# 512kB-v11.net
KiCad netlist of a schematic drawn in EAGLE
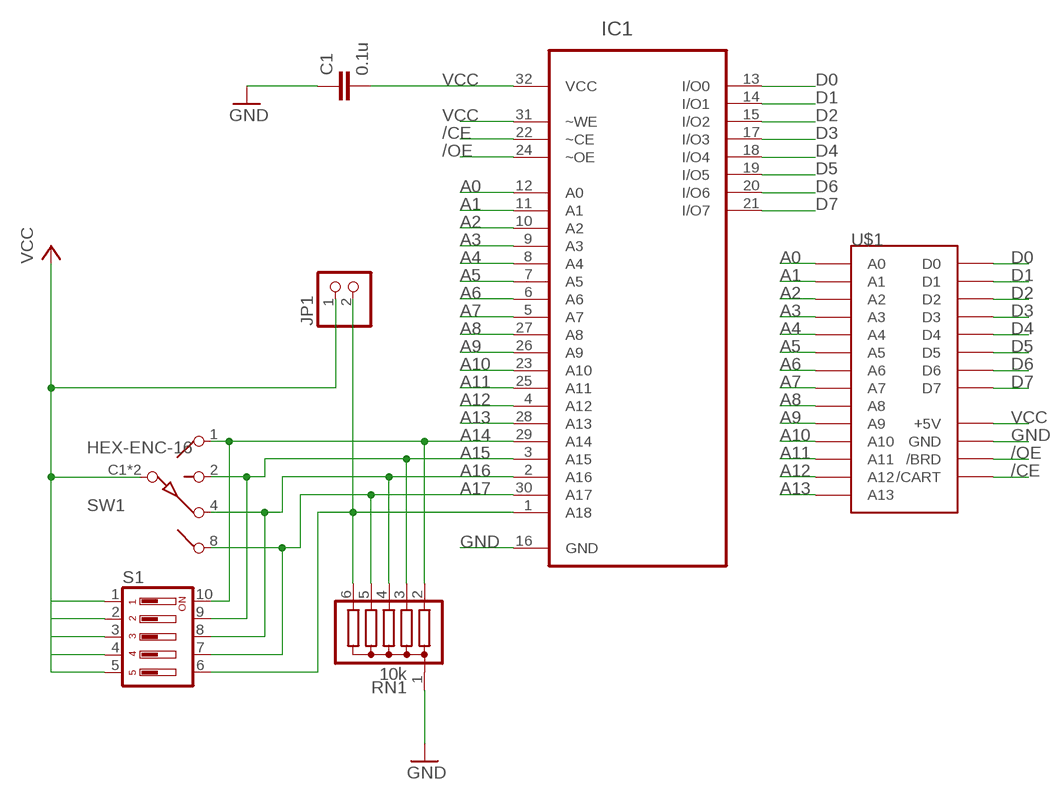
[diagram p0: schematic, sheet 1]

(export (version "E")
  (design (tool "Eeschema 10.0.6"))
  (components
    (comp (ref "C1")
      (value "0.1u")
      (footprint "eagle-import:C050-024X044")
      (libsource (lib "eagle-import") (part "C-EU050-024X044"))
    )
    (comp (ref "IC1")
      (value "AT29C040")
      (footprint "eagle-import:DIP254P1524X482-32")
      (libsource (lib "eagle-import") (part "AT29C040"))
    )
    (comp (ref "JP1")
      (value "PINHD-1X2")
      (footprint "eagle-import:1X02")
      (libsource (lib "eagle-import") (part "PINHD-1X2"))
    )
    (comp (ref "RN1")
      (value "10k")
      (footprint "eagle-import:SIL6")
      (libsource (lib "eagle-import") (part "G05R"))
    )
    (comp (ref "S1")
      (value "DIP05YL")
      (footprint "eagle-import:DIP05YL")
      (libsource (lib "eagle-import") (part "DIP05YL"))
    )
    (comp (ref "SW1")
      (value "HEX-ENC-16")
      (footprint "eagle-import:SW-C16")
      (libsource (lib "eagle-import") (part "SW-C16"))
    )
    (comp (ref "U$1")
      (value "TVC-CARD+")
      (footprint "eagle-import:TVC-CART-CARD")
      (libsource (lib "eagle-import") (part "TVC-CARD+"))
    )
  )
  (nets
    (net (code "1") (name "/A0") (class "Default")
      (node (ref "IC1") (pin "12") (pinfunction "A0_12") (pintype "input"))
      (node (ref "U$1") (pin "TOP25") (pinfunction "A0_TOP25") (pintype "bidirectional"))
    )
    (net (code "2") (name "/A1") (class "Default")
      (node (ref "IC1") (pin "11") (pinfunction "A1_11") (pintype "input"))
      (node (ref "U$1") (pin "TOP2") (pinfunction "A1_TOP2") (pintype "bidirectional"))
    )
    (net (code "3") (name "/A2") (class "Default")
      (node (ref "IC1") (pin "10") (pinfunction "A2_10") (pintype "input"))
      (node (ref "U$1") (pin "TOP24") (pinfunction "A2_TOP24") (pintype "bidirectional"))
    )
    (net (code "4") (name "/A3") (class "Default")
      (node (ref "IC1") (pin "9") (pinfunction "A3_9") (pintype "input"))
      (node (ref "U$1") (pin "TOP1") (pinfunction "A3_TOP1") (pintype "bidirectional"))
    )
    (net (code "5") (name "/A4") (class "Default")
      (node (ref "IC1") (pin "8") (pinfunction "A4_8") (pintype "input"))
      (node (ref "U$1") (pin "TOP21") (pinfunction "A4_TOP21") (pintype "bidirectional"))
    )
    (net (code "6") (name "/A5") (class "Default")
      (node (ref "IC1") (pin "7") (pinfunction "A5_7") (pintype "input"))
      (node (ref "U$1") (pin "TOP14") (pinfunction "A5_TOP14") (pintype "bidirectional"))
    )
    (net (code "7") (name "/A6") (class "Default")
      (node (ref "IC1") (pin "6") (pinfunction "A6_6") (pintype "input"))
      (node (ref "U$1") (pin "TOP18") (pinfunction "A6_TOP18") (pintype "bidirectional"))
    )
    (net (code "8") (name "/A7") (class "Default")
      (node (ref "IC1") (pin "5") (pinfunction "A7_5") (pintype "input"))
      (node (ref "U$1") (pin "TOP17") (pinfunction "A7_TOP17") (pintype "bidirectional"))
    )
    (net (code "9") (name "/A8") (class "Default")
      (node (ref "IC1") (pin "27") (pinfunction "A8_27") (pintype "input"))
      (node (ref "U$1") (pin "TOP15") (pinfunction "A8_TOP15") (pintype "bidirectional"))
    )
    (net (code "10") (name "/A9") (class "Default")
      (node (ref "IC1") (pin "26") (pinfunction "A9_26") (pintype "input"))
      (node (ref "U$1") (pin "TOP19") (pinfunction "A9_TOP19") (pintype "bidirectional"))
    )
    (net (code "11") (name "/A10") (class "Default")
      (node (ref "IC1") (pin "23") (pinfunction "A10_23") (pintype "input"))
      (node (ref "U$1") (pin "TOP22") (pinfunction "A10_TOP22") (pintype "bidirectional"))
    )
    (net (code "12") (name "/A11") (class "Default")
      (node (ref "IC1") (pin "25") (pinfunction "A11_25") (pintype "input"))
      (node (ref "U$1") (pin "TOP20") (pinfunction "A11_TOP20") (pintype "bidirectional"))
    )
    (net (code "13") (name "/A12") (class "Default")
      (node (ref "IC1") (pin "4") (pinfunction "A12_4") (pintype "input"))
      (node (ref "U$1") (pin "TOP16") (pinfunction "A12_TOP16") (pintype "bidirectional"))
    )
    (net (code "14") (name "/A13") (class "Default")
      (node (ref "IC1") (pin "28") (pinfunction "A13_28") (pintype "input"))
      (node (ref "U$1") (pin "TOP23") (pinfunction "A13_TOP23") (pintype "bidirectional"))
    )
    (net (code "15") (name "/A14") (class "Default")
      (node (ref "IC1") (pin "29") (pinfunction "A14_29") (pintype "input"))
      (node (ref "RN1") (pin "2") (pinfunction "2_2") (pintype "passive"))
      (node (ref "S1") (pin "10") (pinfunction "10_10") (pintype "passive"))
      (node (ref "SW1") (pin "1") (pinfunction "1_1") (pintype "passive"))
    )
    (net (code "16") (name "/A15") (class "Default")
      (node (ref "IC1") (pin "3") (pinfunction "A15_3") (pintype "input"))
      (node (ref "RN1") (pin "3") (pinfunction "3_3") (pintype "passive"))
      (node (ref "S1") (pin "9") (pinfunction "9_9") (pintype "passive"))
      (node (ref "SW1") (pin "2") (pinfunction "2_2") (pintype "passive"))
    )
    (net (code "17") (name "/A16") (class "Default")
      (node (ref "IC1") (pin "2") (pinfunction "A16_2") (pintype "input"))
      (node (ref "RN1") (pin "4") (pinfunction "4_4") (pintype "passive"))
      (node (ref "S1") (pin "8") (pinfunction "8_8") (pintype "passive"))
      (node (ref "SW1") (pin "4") (pinfunction "4_4") (pintype "passive"))
    )
    (net (code "18") (name "/A17") (class "Default")
      (node (ref "IC1") (pin "30") (pinfunction "A17_30") (pintype "input"))
      (node (ref "RN1") (pin "5") (pinfunction "5_5") (pintype "passive"))
      (node (ref "S1") (pin "7") (pinfunction "7_7") (pintype "passive"))
      (node (ref "SW1") (pin "8") (pinfunction "8_8") (pintype "passive"))
    )
    (net (code "19") (name "/D0") (class "Default")
      (node (ref "IC1") (pin "13") (pinfunction "I/O0_13") (pintype "bidirectional"))
      (node (ref "U$1") (pin "TOP4") (pinfunction "D0_TOP4") (pintype "bidirectional"))
    )
    (net (code "20") (name "/D1") (class "Default")
      (node (ref "IC1") (pin "14") (pinfunction "I/O1_14") (pintype "bidirectional"))
      (node (ref "U$1") (pin "TOP5") (pinfunction "D1_TOP5") (pintype "bidirectional"))
    )
    (net (code "21") (name "/D2") (class "Default")
      (node (ref "IC1") (pin "15") (pinfunction "I/O2_15") (pintype "bidirectional"))
      (node (ref "U$1") (pin "TOP6") (pinfunction "D2_TOP6") (pintype "bidirectional"))
    )
    (net (code "22") (name "/D3") (class "Default")
      (node (ref "IC1") (pin "17") (pinfunction "I/O3_17") (pintype "bidirectional"))
      (node (ref "U$1") (pin "TOP7") (pinfunction "D3_TOP7") (pintype "bidirectional"))
    )
    (net (code "23") (name "/D4") (class "Default")
      (node (ref "IC1") (pin "18") (pinfunction "I/O4_18") (pintype "bidirectional"))
      (node (ref "U$1") (pin "TOP8") (pinfunction "D4_TOP8") (pintype "bidirectional"))
    )
    (net (code "24") (name "/D5") (class "Default")
      (node (ref "IC1") (pin "19") (pinfunction "I/O5_19") (pintype "bidirectional"))
      (node (ref "U$1") (pin "TOP9") (pinfunction "D5_TOP9") (pintype "bidirectional"))
    )
    (net (code "25") (name "/D6") (class "Default")
      (node (ref "IC1") (pin "20") (pinfunction "I/O6_20") (pintype "bidirectional"))
      (node (ref "U$1") (pin "TOP10") (pinfunction "D6_TOP10") (pintype "bidirectional"))
    )
    (net (code "26") (name "/D7") (class "Default")
      (node (ref "IC1") (pin "21") (pinfunction "I/O7_21") (pintype "bidirectional"))
      (node (ref "U$1") (pin "TOP3") (pinfunction "D7_TOP3") (pintype "bidirectional"))
    )
    (net (code "27") (name "/{slash}CE") (class "Default")
      (node (ref "IC1") (pin "22") (pinfunction "~{CE}_22") (pintype "input"))
      (node (ref "U$1") (pin "BTM23") (pinfunction "/CART_BTM23") (pintype "bidirectional"))
    )
    (net (code "28") (name "/{slash}OE") (class "Default")
      (node (ref "IC1") (pin "24") (pinfunction "~{OE}_24") (pintype "input"))
      (node (ref "U$1") (pin "BTM24") (pinfunction "/BRD_BTM24") (pintype "bidirectional"))
    )
    (net (code "29") (name "GND") (class "Default")
      (node (ref "C1") (pin "1") (pinfunction "1_1") (pintype "passive"))
      (node (ref "IC1") (pin "16") (pinfunction "GND_16") (pintype "passive"))
      (node (ref "RN1") (pin "1") (pinfunction "1_1") (pintype "passive"))
      (node (ref "U$1") (pin "BTM1") (pinfunction "GND_BTM1") (pintype "power_in"))
      (node (ref "U$1") (pin "BTM2") (pinfunction "GND_BTM2") (pintype "power_in"))
      (node (ref "U$1") (pin "BTM3") (pinfunction "GND_BTM3") (pintype "power_in"))
      (node (ref "U$1") (pin "BTM4") (pinfunction "GND_BTM4") (pintype "power_in"))
      (node (ref "U$1") (pin "BTM5") (pinfunction "GND_BTM5") (pintype "power_in"))
      (node (ref "U$1") (pin "BTM6") (pinfunction "GND_BTM6") (pintype "power_in"))
      (node (ref "U$1") (pin "BTM7") (pinfunction "GND_BTM7") (pintype "power_in"))
      (node (ref "U$1") (pin "BTM8") (pinfunction "GND_BTM8") (pintype "power_in"))
    )
    (net (code "30") (name "Net-(IC1-A18)") (class "Default")
      (node (ref "IC1") (pin "1") (pinfunction "A18_1") (pintype "input"))
      (node (ref "JP1") (pin "2") (pinfunction "2_2") (pintype "passive"))
      (node (ref "RN1") (pin "6") (pinfunction "6_6") (pintype "passive"))
      (node (ref "S1") (pin "6") (pinfunction "6_6") (pintype "passive"))
    )
    (net (code "31") (name "VCC") (class "Default")
      (node (ref "C1") (pin "2") (pinfunction "2_2") (pintype "passive"))
      (node (ref "IC1") (pin "31") (pinfunction "~{WE}_31") (pintype "input"))
      (node (ref "IC1") (pin "32") (pinfunction "VCC_32") (pintype "power_in"))
      (node (ref "JP1") (pin "1") (pinfunction "1_1") (pintype "passive"))
      (node (ref "S1") (pin "1") (pinfunction "1_1") (pintype "passive"))
      (node (ref "S1") (pin "2") (pinfunction "2_2") (pintype "passive"))
      (node (ref "S1") (pin "3") (pinfunction "3_3") (pintype "passive"))
      (node (ref "S1") (pin "4") (pinfunction "4_4") (pintype "passive"))
      (node (ref "S1") (pin "5") (pinfunction "5_5") (pintype "passive"))
      (node (ref "SW1") (pin "C1") (pinfunction "C_C1") (pintype "passive"))
      (node (ref "SW1") (pin "C2") (pinfunction "C_C2") (pintype "passive"))
      (node (ref "U$1") (pin "BTM10") (pinfunction "+5V_BTM10") (pintype "power_in"))
      (node (ref "U$1") (pin "BTM11") (pinfunction "+5V_BTM11") (pintype "power_in"))
      (node (ref "U$1") (pin "BTM12") (pinfunction "+5V_BTM12") (pintype "power_in"))
      (node (ref "U$1") (pin "BTM13") (pinfunction "+5V_BTM13") (pintype "power_in"))
      (node (ref "U$1") (pin "BTM14") (pinfunction "+5V_BTM14") (pintype "power_in"))
      (node (ref "U$1") (pin "BTM15") (pinfunction "+5V_BTM15") (pintype "power_in"))
      (node (ref "U$1") (pin "BTM16") (pinfunction "+5V_BTM16") (pintype "power_in"))
      (node (ref "U$1") (pin "BTM17") (pinfunction "+5V_BTM17") (pintype "power_in"))
    )
  )
)
